# ir-splitter.net
KiCad netlist of a schematic drawn in EAGLE
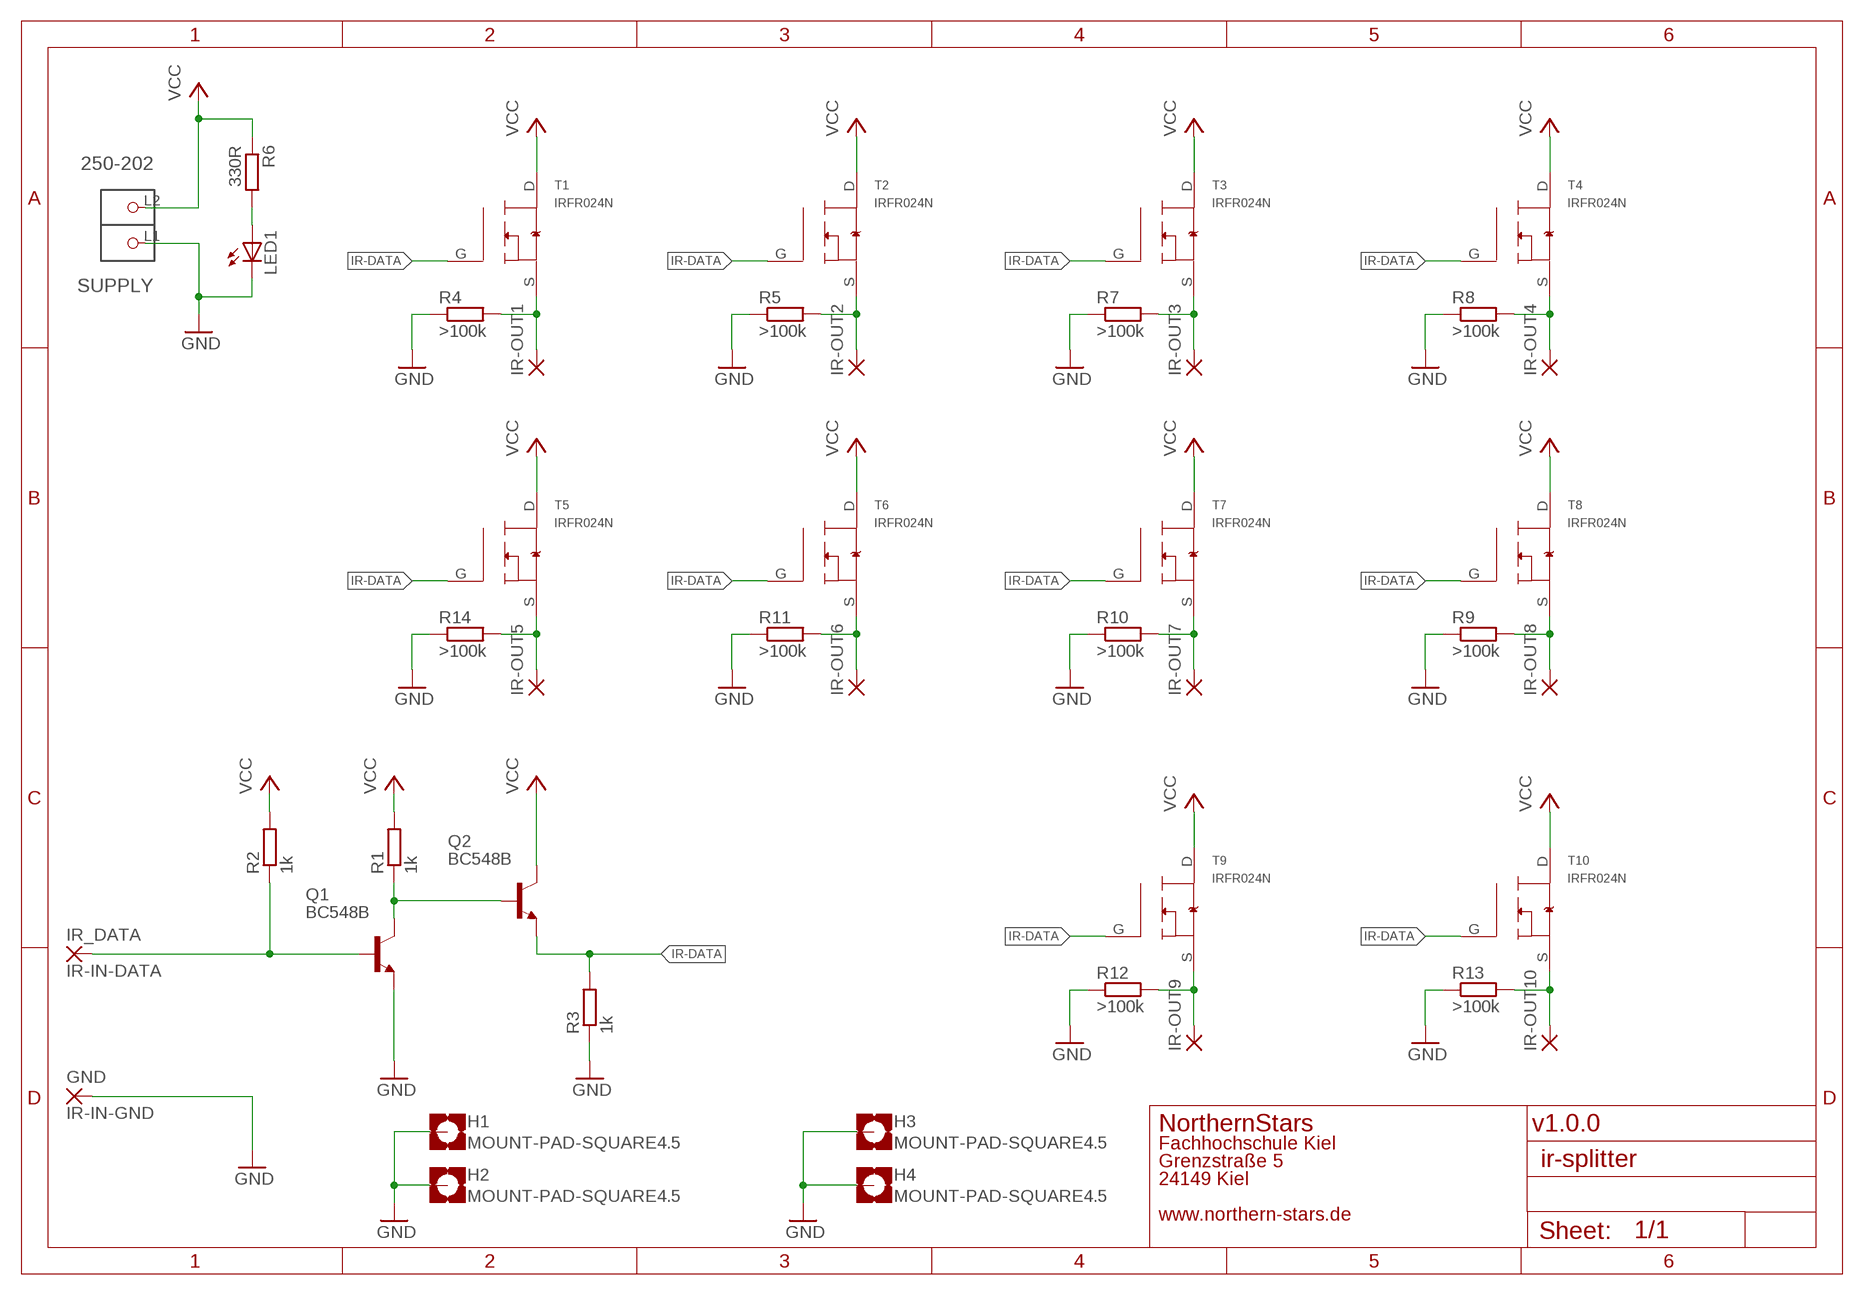
[diagram p0: schematic, sheet 1]

(export (version "E")
  (design (tool "Eeschema 10.0.6"))
  (components
    (comp (ref "GND")
      (value "IR-IN-GND")
      (footprint "eagle-import:3,81_1,4")
      (libsource (lib "eagle-import") (part "3,81/1,4"))
    )
    (comp (ref "H1")
      (value "MOUNT-PAD-SQUARE4.5")
      (footprint "eagle-import:4,5-PAD-SQUARE")
      (libsource (lib "eagle-import") (part "MOUNT-PAD-SQUARE4.5"))
    )
    (comp (ref "H2")
      (value "MOUNT-PAD-SQUARE4.5")
      (footprint "eagle-import:4,5-PAD-SQUARE")
      (libsource (lib "eagle-import") (part "MOUNT-PAD-SQUARE4.5"))
    )
    (comp (ref "H3")
      (value "MOUNT-PAD-SQUARE4.5")
      (footprint "eagle-import:4,5-PAD-SQUARE")
      (libsource (lib "eagle-import") (part "MOUNT-PAD-SQUARE4.5"))
    )
    (comp (ref "H4")
      (value "MOUNT-PAD-SQUARE4.5")
      (footprint "eagle-import:4,5-PAD-SQUARE")
      (libsource (lib "eagle-import") (part "MOUNT-PAD-SQUARE4.5"))
    )
    (comp (ref "IR-OUT1")
      (value "3,81/1,4")
      (footprint "eagle-import:3,81_1,4")
      (libsource (lib "eagle-import") (part "3,81/1,4"))
    )
    (comp (ref "IR-OUT2")
      (value "3,81/1,4")
      (footprint "eagle-import:3,81_1,4")
      (libsource (lib "eagle-import") (part "3,81/1,4"))
    )
    (comp (ref "IR-OUT3")
      (value "3,81/1,4")
      (footprint "eagle-import:3,81_1,4")
      (libsource (lib "eagle-import") (part "3,81/1,4"))
    )
    (comp (ref "IR-OUT4")
      (value "3,81/1,4")
      (footprint "eagle-import:3,81_1,4")
      (libsource (lib "eagle-import") (part "3,81/1,4"))
    )
    (comp (ref "IR-OUT5")
      (value "3,81/1,4")
      (footprint "eagle-import:3,81_1,4")
      (libsource (lib "eagle-import") (part "3,81/1,4"))
    )
    (comp (ref "IR-OUT6")
      (value "3,81/1,4")
      (footprint "eagle-import:3,81_1,4")
      (libsource (lib "eagle-import") (part "3,81/1,4"))
    )
    (comp (ref "IR-OUT7")
      (value "3,81/1,4")
      (footprint "eagle-import:3,81_1,4")
      (libsource (lib "eagle-import") (part "3,81/1,4"))
    )
    (comp (ref "IR-OUT8")
      (value "3,81/1,4")
      (footprint "eagle-import:3,81_1,4")
      (libsource (lib "eagle-import") (part "3,81/1,4"))
    )
    (comp (ref "IR-OUT9")
      (value "3,81/1,4")
      (footprint "eagle-import:3,81_1,4")
      (libsource (lib "eagle-import") (part "3,81/1,4"))
    )
    (comp (ref "IR-OUT10")
      (value "3,81/1,4")
      (footprint "eagle-import:3,81_1,4")
      (libsource (lib "eagle-import") (part "3,81/1,4"))
    )
    (comp (ref "IR_DATA")
      (value "IR-IN-DATA")
      (footprint "eagle-import:3,81_1,4")
      (libsource (lib "eagle-import") (part "3,81/1,4"))
    )
    (comp (ref "LED1")
      (value "LEDCHIPLED_1206")
      (footprint "eagle-import:CHIPLED_1206")
      (libsource (lib "eagle-import") (part "LEDCHIPLED_1206"))
    )
    (comp (ref "Q1")
      (value "BC548B")
      (footprint "eagle-import:TO92-EBC")
      (libsource (lib "eagle-import") (part "BC548B"))
    )
    (comp (ref "Q2")
      (value "BC548B")
      (footprint "eagle-import:TO92-EBC")
      (libsource (lib "eagle-import") (part "BC548B"))
    )
    (comp (ref "R1")
      (value "1k")
      (footprint "eagle-import:R1206")
      (libsource (lib "eagle-import") (part "R-EU_R1206"))
    )
    (comp (ref "R2")
      (value "1k")
      (footprint "eagle-import:R1206")
      (libsource (lib "eagle-import") (part "R-EU_R1206"))
    )
    (comp (ref "R3")
      (value "1k")
      (footprint "eagle-import:R1206")
      (libsource (lib "eagle-import") (part "R-EU_R1206"))
    )
    (comp (ref "R4")
      (value ">100k")
      (footprint "eagle-import:R1206")
      (libsource (lib "eagle-import") (part "R-EU_R1206"))
    )
    (comp (ref "R5")
      (value ">100k")
      (footprint "eagle-import:R1206")
      (libsource (lib "eagle-import") (part "R-EU_R1206"))
    )
    (comp (ref "R6")
      (value "330R")
      (footprint "eagle-import:R1206")
      (libsource (lib "eagle-import") (part "R-EU_R1206"))
    )
    (comp (ref "R7")
      (value ">100k")
      (footprint "eagle-import:R1206")
      (libsource (lib "eagle-import") (part "R-EU_R1206"))
    )
    (comp (ref "R8")
      (value ">100k")
      (footprint "eagle-import:R1206")
      (libsource (lib "eagle-import") (part "R-EU_R1206"))
    )
    (comp (ref "R9")
      (value ">100k")
      (footprint "eagle-import:R1206")
      (libsource (lib "eagle-import") (part "R-EU_R1206"))
    )
    (comp (ref "R10")
      (value ">100k")
      (footprint "eagle-import:R1206")
      (libsource (lib "eagle-import") (part "R-EU_R1206"))
    )
    (comp (ref "R11")
      (value ">100k")
      (footprint "eagle-import:R1206")
      (libsource (lib "eagle-import") (part "R-EU_R1206"))
    )
    (comp (ref "R12")
      (value ">100k")
      (footprint "eagle-import:R1206")
      (libsource (lib "eagle-import") (part "R-EU_R1206"))
    )
    (comp (ref "R13")
      (value ">100k")
      (footprint "eagle-import:R1206")
      (libsource (lib "eagle-import") (part "R-EU_R1206"))
    )
    (comp (ref "R14")
      (value ">100k")
      (footprint "eagle-import:R1206")
      (libsource (lib "eagle-import") (part "R-EU_R1206"))
    )
    (comp (ref "SUPPLY")
      (value "250-202")
      (footprint "eagle-import:P-250-202")
      (libsource (lib "eagle-import") (part "250-202"))
    )
    (comp (ref "T1")
      (value "IRFR024N")
      (footprint "eagle-import:D-PAK")
      (libsource (lib "eagle-import") (part "IRLR3915PBF"))
    )
    (comp (ref "T2")
      (value "IRFR024N")
      (footprint "eagle-import:D-PAK")
      (libsource (lib "eagle-import") (part "IRLR3915PBF"))
    )
    (comp (ref "T3")
      (value "IRFR024N")
      (footprint "eagle-import:D-PAK")
      (libsource (lib "eagle-import") (part "IRLR3915PBF"))
    )
    (comp (ref "T4")
      (value "IRFR024N")
      (footprint "eagle-import:D-PAK")
      (libsource (lib "eagle-import") (part "IRLR3915PBF"))
    )
    (comp (ref "T5")
      (value "IRFR024N")
      (footprint "eagle-import:D-PAK")
      (libsource (lib "eagle-import") (part "IRLR3915PBF"))
    )
    (comp (ref "T6")
      (value "IRFR024N")
      (footprint "eagle-import:D-PAK")
      (libsource (lib "eagle-import") (part "IRLR3915PBF"))
    )
    (comp (ref "T7")
      (value "IRFR024N")
      (footprint "eagle-import:D-PAK")
      (libsource (lib "eagle-import") (part "IRLR3915PBF"))
    )
    (comp (ref "T8")
      (value "IRFR024N")
      (footprint "eagle-import:D-PAK")
      (libsource (lib "eagle-import") (part "IRLR3915PBF"))
    )
    (comp (ref "T9")
      (value "IRFR024N")
      (footprint "eagle-import:D-PAK")
      (libsource (lib "eagle-import") (part "IRLR3915PBF"))
    )
    (comp (ref "T10")
      (value "IRFR024N")
      (footprint "eagle-import:D-PAK")
      (libsource (lib "eagle-import") (part "IRLR3915PBF"))
    )
  )
  (nets
    (net (code "1") (name "GND") (class "Default")
      (node (ref "GND") (pin "1") (pinfunction "P_1") (pintype "passive"))
      (node (ref "H1") (pin "B4,5") (pinfunction "MOUNT_B4,5") (pintype "passive"))
      (node (ref "H2") (pin "B4,5") (pinfunction "MOUNT_B4,5") (pintype "passive"))
      (node (ref "H3") (pin "B4,5") (pinfunction "MOUNT_B4,5") (pintype "passive"))
      (node (ref "H4") (pin "B4,5") (pinfunction "MOUNT_B4,5") (pintype "passive"))
      (node (ref "LED1") (pin "C") (pinfunction "C_C") (pintype "passive"))
      (node (ref "Q1") (pin "E") (pinfunction "E_E") (pintype "passive"))
      (node (ref "R10") (pin "1") (pinfunction "1_1") (pintype "passive"))
      (node (ref "R11") (pin "1") (pinfunction "1_1") (pintype "passive"))
      (node (ref "R12") (pin "1") (pinfunction "1_1") (pintype "passive"))
      (node (ref "R13") (pin "1") (pinfunction "1_1") (pintype "passive"))
      (node (ref "R14") (pin "1") (pinfunction "1_1") (pintype "passive"))
      (node (ref "R3") (pin "1") (pinfunction "1_1") (pintype "passive"))
      (node (ref "R4") (pin "1") (pinfunction "1_1") (pintype "passive"))
      (node (ref "R5") (pin "1") (pinfunction "1_1") (pintype "passive"))
      (node (ref "R7") (pin "1") (pinfunction "1_1") (pintype "passive"))
      (node (ref "R8") (pin "1") (pinfunction "1_1") (pintype "passive"))
      (node (ref "R9") (pin "1") (pinfunction "1_1") (pintype "passive"))
      (node (ref "SUPPLY") (pin "L1") (pinfunction "P1_L1") (pintype "bidirectional"))
    )
    (net (code "2") (name "IR-DATA") (class "Default")
      (node (ref "Q2") (pin "E") (pinfunction "E_E") (pintype "passive"))
      (node (ref "R3") (pin "2") (pinfunction "2_2") (pintype "passive"))
      (node (ref "T1") (pin "G") (pinfunction "G_G") (pintype "bidirectional"))
      (node (ref "T10") (pin "G") (pinfunction "G_G") (pintype "bidirectional"))
      (node (ref "T2") (pin "G") (pinfunction "G_G") (pintype "bidirectional"))
      (node (ref "T3") (pin "G") (pinfunction "G_G") (pintype "bidirectional"))
      (node (ref "T4") (pin "G") (pinfunction "G_G") (pintype "bidirectional"))
      (node (ref "T5") (pin "G") (pinfunction "G_G") (pintype "bidirectional"))
      (node (ref "T6") (pin "G") (pinfunction "G_G") (pintype "bidirectional"))
      (node (ref "T7") (pin "G") (pinfunction "G_G") (pintype "bidirectional"))
      (node (ref "T8") (pin "G") (pinfunction "G_G") (pintype "bidirectional"))
      (node (ref "T9") (pin "G") (pinfunction "G_G") (pintype "bidirectional"))
    )
    (net (code "3") (name "Net-(IR-OUT1-P)") (class "Default")
      (node (ref "IR-OUT1") (pin "1") (pinfunction "P_1") (pintype "passive"))
      (node (ref "R4") (pin "2") (pinfunction "2_2") (pintype "passive"))
      (node (ref "T1") (pin "S") (pinfunction "P$3_S") (pintype "bidirectional"))
    )
    (net (code "4") (name "Net-(IR-OUT2-P)") (class "Default")
      (node (ref "IR-OUT2") (pin "1") (pinfunction "P_1") (pintype "passive"))
      (node (ref "R5") (pin "2") (pinfunction "2_2") (pintype "passive"))
      (node (ref "T2") (pin "S") (pinfunction "P$3_S") (pintype "bidirectional"))
    )
    (net (code "5") (name "Net-(IR-OUT3-P)") (class "Default")
      (node (ref "IR-OUT3") (pin "1") (pinfunction "P_1") (pintype "passive"))
      (node (ref "R7") (pin "2") (pinfunction "2_2") (pintype "passive"))
      (node (ref "T3") (pin "S") (pinfunction "P$3_S") (pintype "bidirectional"))
    )
    (net (code "6") (name "Net-(IR-OUT4-P)") (class "Default")
      (node (ref "IR-OUT4") (pin "1") (pinfunction "P_1") (pintype "passive"))
      (node (ref "R8") (pin "2") (pinfunction "2_2") (pintype "passive"))
      (node (ref "T4") (pin "S") (pinfunction "P$3_S") (pintype "bidirectional"))
    )
    (net (code "7") (name "Net-(IR-OUT5-P)") (class "Default")
      (node (ref "IR-OUT5") (pin "1") (pinfunction "P_1") (pintype "passive"))
      (node (ref "R14") (pin "2") (pinfunction "2_2") (pintype "passive"))
      (node (ref "T5") (pin "S") (pinfunction "P$3_S") (pintype "bidirectional"))
    )
    (net (code "8") (name "Net-(IR-OUT6-P)") (class "Default")
      (node (ref "IR-OUT6") (pin "1") (pinfunction "P_1") (pintype "passive"))
      (node (ref "R11") (pin "2") (pinfunction "2_2") (pintype "passive"))
      (node (ref "T6") (pin "S") (pinfunction "P$3_S") (pintype "bidirectional"))
    )
    (net (code "9") (name "Net-(IR-OUT7-P)") (class "Default")
      (node (ref "IR-OUT7") (pin "1") (pinfunction "P_1") (pintype "passive"))
      (node (ref "R10") (pin "2") (pinfunction "2_2") (pintype "passive"))
      (node (ref "T7") (pin "S") (pinfunction "P$3_S") (pintype "bidirectional"))
    )
    (net (code "10") (name "Net-(IR-OUT8-P)") (class "Default")
      (node (ref "IR-OUT8") (pin "1") (pinfunction "P_1") (pintype "passive"))
      (node (ref "R9") (pin "2") (pinfunction "2_2") (pintype "passive"))
      (node (ref "T8") (pin "S") (pinfunction "P$3_S") (pintype "bidirectional"))
    )
    (net (code "11") (name "Net-(IR-OUT9-P)") (class "Default")
      (node (ref "IR-OUT9") (pin "1") (pinfunction "P_1") (pintype "passive"))
      (node (ref "R12") (pin "2") (pinfunction "2_2") (pintype "passive"))
      (node (ref "T9") (pin "S") (pinfunction "P$3_S") (pintype "bidirectional"))
    )
    (net (code "12") (name "Net-(IR-OUT10-P)") (class "Default")
      (node (ref "IR-OUT10") (pin "1") (pinfunction "P_1") (pintype "passive"))
      (node (ref "R13") (pin "2") (pinfunction "2_2") (pintype "passive"))
      (node (ref "T10") (pin "S") (pinfunction "P$3_S") (pintype "bidirectional"))
    )
    (net (code "13") (name "Net-(IR_DATA-P)") (class "Default")
      (node (ref "IR_DATA") (pin "1") (pinfunction "P_1") (pintype "passive"))
      (node (ref "Q1") (pin "B") (pinfunction "B_B") (pintype "passive"))
      (node (ref "R2") (pin "1") (pinfunction "1_1") (pintype "passive"))
    )
    (net (code "14") (name "Net-(LED1-PadA)") (class "Default")
      (node (ref "LED1") (pin "A") (pinfunction "A_A") (pintype "passive"))
      (node (ref "R6") (pin "2") (pinfunction "2_2") (pintype "passive"))
    )
    (net (code "15") (name "Net-(Q1-PadC)") (class "Default")
      (node (ref "Q1") (pin "C") (pinfunction "C_C") (pintype "passive"))
      (node (ref "Q2") (pin "B") (pinfunction "B_B") (pintype "passive"))
      (node (ref "R1") (pin "1") (pinfunction "1_1") (pintype "passive"))
    )
    (net (code "16") (name "VCC") (class "Default")
      (node (ref "Q2") (pin "C") (pinfunction "C_C") (pintype "passive"))
      (node (ref "R1") (pin "2") (pinfunction "2_2") (pintype "passive"))
      (node (ref "R2") (pin "2") (pinfunction "2_2") (pintype "passive"))
      (node (ref "R6") (pin "1") (pinfunction "1_1") (pintype "passive"))
      (node (ref "SUPPLY") (pin "L2") (pinfunction "P2_L2") (pintype "bidirectional"))
      (node (ref "T1") (pin "D") (pinfunction "P$2_D") (pintype "bidirectional"))
      (node (ref "T10") (pin "D") (pinfunction "P$2_D") (pintype "bidirectional"))
      (node (ref "T2") (pin "D") (pinfunction "P$2_D") (pintype "bidirectional"))
      (node (ref "T3") (pin "D") (pinfunction "P$2_D") (pintype "bidirectional"))
      (node (ref "T4") (pin "D") (pinfunction "P$2_D") (pintype "bidirectional"))
      (node (ref "T5") (pin "D") (pinfunction "P$2_D") (pintype "bidirectional"))
      (node (ref "T6") (pin "D") (pinfunction "P$2_D") (pintype "bidirectional"))
      (node (ref "T7") (pin "D") (pinfunction "P$2_D") (pintype "bidirectional"))
      (node (ref "T8") (pin "D") (pinfunction "P$2_D") (pintype "bidirectional"))
      (node (ref "T9") (pin "D") (pinfunction "P$2_D") (pintype "bidirectional"))
    )
  )
)
